# HS_LS_Switch_LOW_PWR.net
KiCad netlist of a schematic drawn in Altium Designer
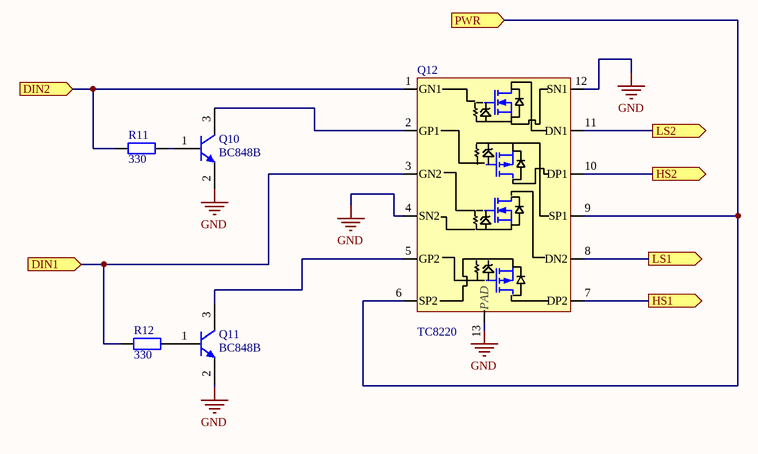
[diagram p0: HS_LS_Switch_LOW_PWR.SchDoc]

(export (version "E")
  (design (tool "Eeschema 10.0.6"))
  (components
    (comp (ref "Q10")
      (value "BC848B")
      (footprint "SOT23_N")
      (description "NPN Silicon AF Transistor, 30 V VCEO, 100 mA IC, SOT23, Reel, Green")
      (fields (field (name "MANUFACTURER") "Infineon"))
      (libsource (lib "Datalogger") (part "BC848B"))
    )
    (comp (ref "Q11")
      (value "BC848B")
      (footprint "SOT23_N")
      (description "NPN Silicon AF Transistor, 30 V VCEO, 100 mA IC, SOT23, Reel, Green")
      (fields (field (name "MANUFACTURER") "Infineon"))
      (libsource (lib "Datalogger") (part "BC848B"))
    )
    (comp (ref "Q12")
      (value "TC8220")
      (footprint "DFN400X400X100-12")
      (description "Two pair, N- & P-Channel Enhancement MOSFET")
      (libsource (lib "Datalogger") (part "TC8220"))
    )
    (comp (ref "R11")
      (value "330")
      (footprint "RES-1206_M")
      (description "Resistor")
      (fields (field (name "PUBLISHER") "Altium Limited"))
      (libsource (lib "Datalogger") (part "Res2"))
    )
    (comp (ref "R12")
      (value "330")
      (footprint "RES-1206_M")
      (description "Resistor")
      (fields (field (name "PUBLISHER") "Altium Limited"))
      (libsource (lib "Datalogger") (part "Res2"))
    )
  )
  (nets
    (net (code "1") (name "/DIN1") (class "Default")
      (node (ref "Q12") (pin "3") (pinfunction "GN2_3") (pintype "passive"))
      (node (ref "R12") (pin "1") (pinfunction "1_1") (pintype "passive"))
    )
    (net (code "2") (name "/DIN2") (class "Default")
      (node (ref "Q12") (pin "1") (pinfunction "GN1_1") (pintype "passive"))
      (node (ref "R11") (pin "1") (pinfunction "1_1") (pintype "passive"))
    )
    (net (code "3") (name "/HS1") (class "Default")
      (node (ref "Q12") (pin "7") (pinfunction "DP2_7") (pintype "passive"))
    )
    (net (code "4") (name "/HS2") (class "Default")
      (node (ref "Q12") (pin "10") (pinfunction "DP1_10") (pintype "passive"))
    )
    (net (code "5") (name "/LS1") (class "Default")
      (node (ref "Q12") (pin "8") (pinfunction "DN2_8") (pintype "passive"))
    )
    (net (code "6") (name "/LS2") (class "Default")
      (node (ref "Q12") (pin "11") (pinfunction "DN1_11") (pintype "passive"))
    )
    (net (code "7") (name "/PWR") (class "Default")
      (node (ref "Q12") (pin "6") (pinfunction "SP2_6") (pintype "passive"))
      (node (ref "Q12") (pin "9") (pinfunction "SP1_9") (pintype "passive"))
    )
    (net (code "8") (name "GND") (class "Default")
      (node (ref "Q10") (pin "2") (pinfunction "E_2") (pintype "passive"))
      (node (ref "Q11") (pin "2") (pinfunction "E_2") (pintype "passive"))
      (node (ref "Q12") (pin "12") (pinfunction "SN1_12") (pintype "passive"))
      (node (ref "Q12") (pin "13") (pinfunction "PAD_13") (pintype "passive"))
      (node (ref "Q12") (pin "4") (pinfunction "SN2_4") (pintype "passive"))
    )
    (net (code "9") (name "Net-(Q10-B)") (class "Default")
      (node (ref "Q10") (pin "1") (pinfunction "B_1") (pintype "passive"))
      (node (ref "R11") (pin "2") (pinfunction "2_2") (pintype "passive"))
    )
    (net (code "10") (name "Net-(Q10-C)") (class "Default")
      (node (ref "Q10") (pin "3") (pinfunction "C_3") (pintype "passive"))
      (node (ref "Q12") (pin "2") (pinfunction "GP1_2") (pintype "passive"))
    )
    (net (code "11") (name "Net-(Q11-B)") (class "Default")
      (node (ref "Q11") (pin "1") (pinfunction "B_1") (pintype "passive"))
      (node (ref "R12") (pin "2") (pinfunction "2_2") (pintype "passive"))
    )
    (net (code "12") (name "Net-(Q11-C)") (class "Default")
      (node (ref "Q11") (pin "3") (pinfunction "C_3") (pintype "passive"))
      (node (ref "Q12") (pin "5") (pinfunction "GP2_5") (pintype "passive"))
    )
  )
)
